# Adafruit_HMC5883L_Compas.net
KiCad netlist of a schematic drawn in EAGLE
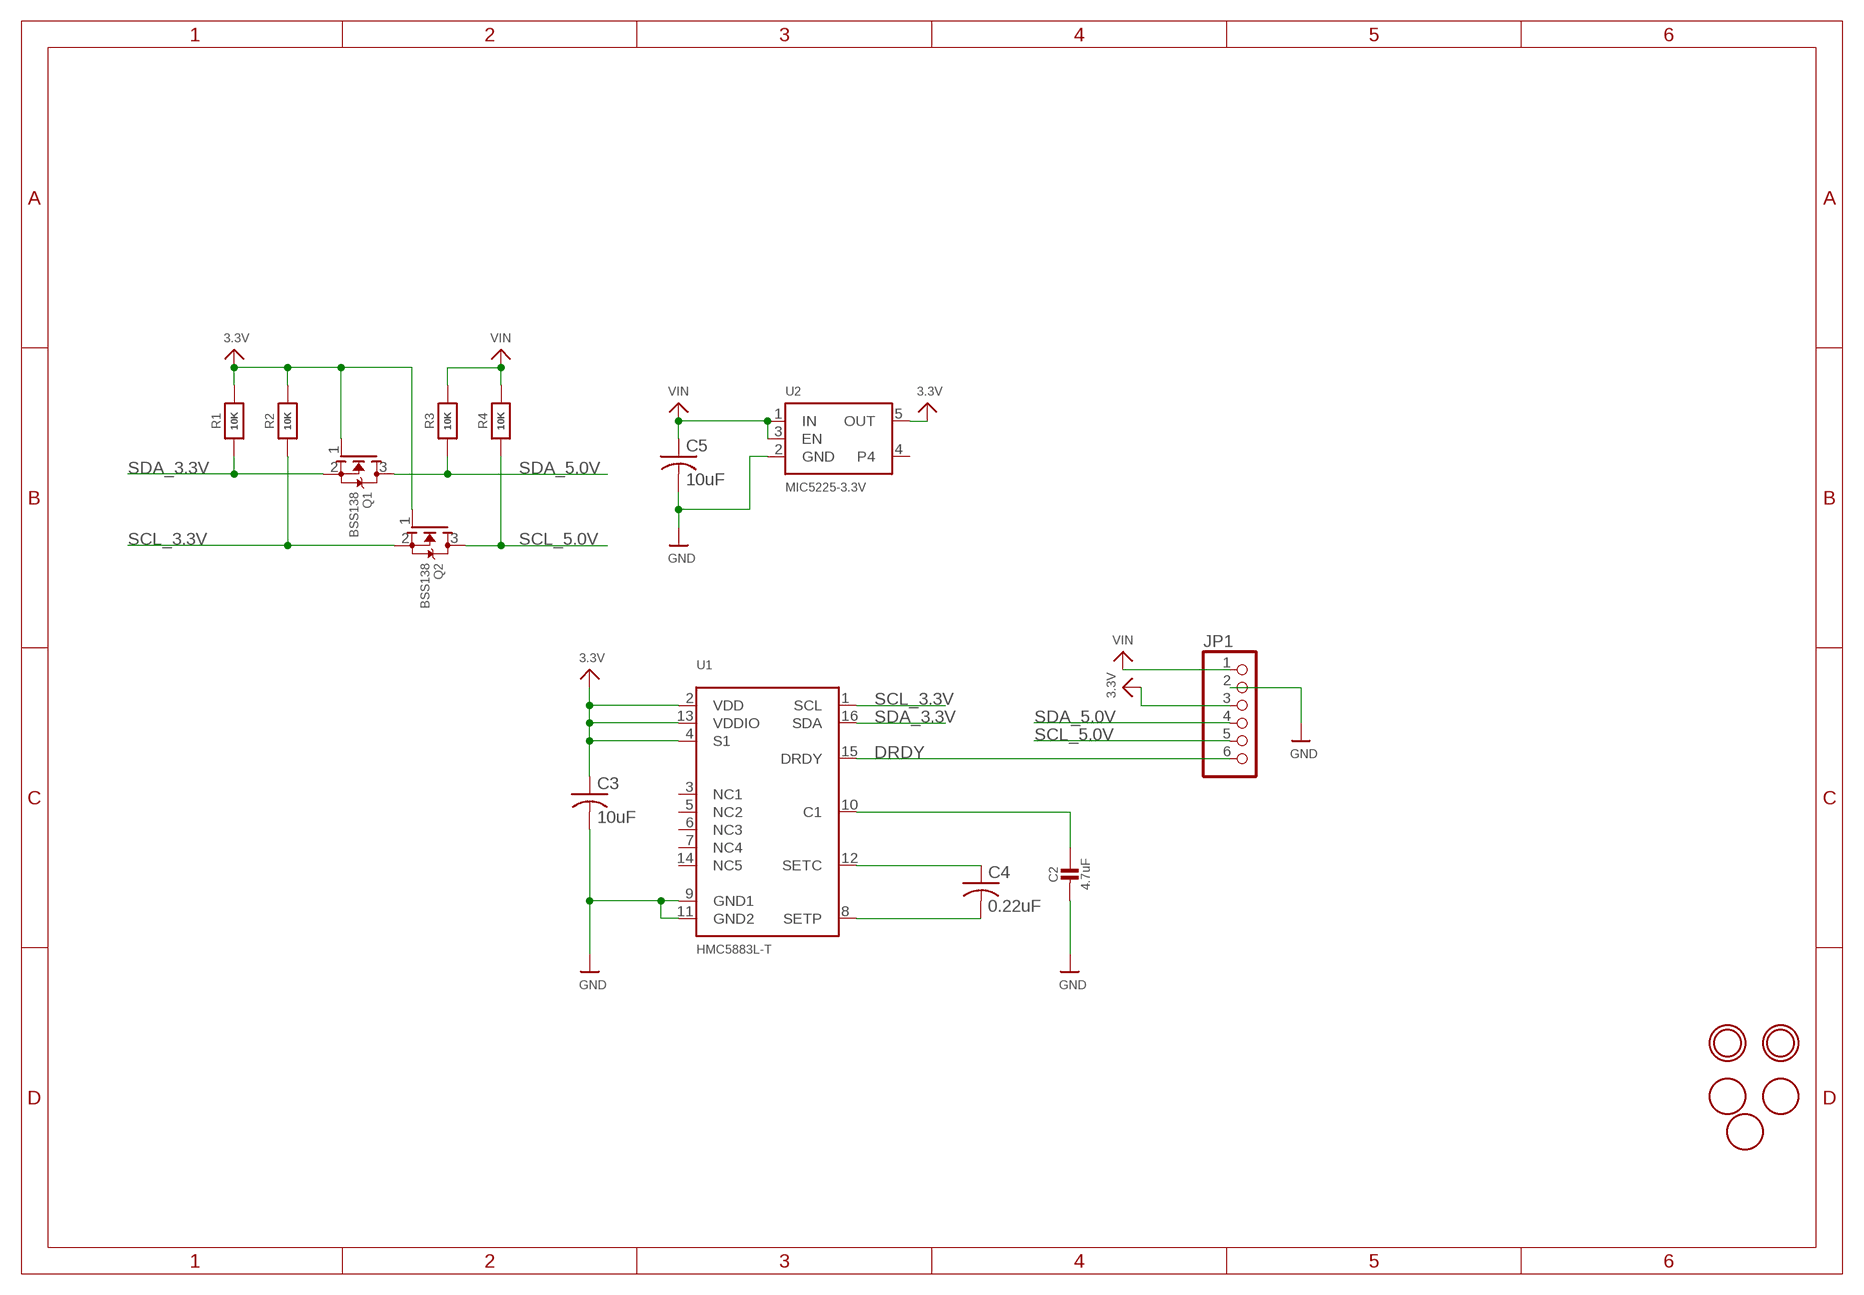
[diagram p0: schematic, sheet 1]

(export (version "E")
  (design (tool "Eeschema 10.0.6"))
  (components
    (comp (ref "C2")
      (value "4.7uF")
      (footprint "eagle-import:0805_10MGAP")
      (libsource (lib "eagle-import") (part "CAP_CERAMIC0805_10MGAP"))
    )
    (comp (ref "C3")
      (value "10uF")
      (footprint "eagle-import:C0805")
      (libsource (lib "eagle-import") (part "C-USC0805"))
    )
    (comp (ref "C4")
      (value "0.22uF")
      (footprint "eagle-import:C0805")
      (libsource (lib "eagle-import") (part "C-USC0805"))
    )
    (comp (ref "C5")
      (value "10uF")
      (footprint "eagle-import:C0805")
      (libsource (lib "eagle-import") (part "C-USC0805"))
    )
    (comp (ref "JP1")
      (value "HEADER-1X676MIL")
      (footprint "eagle-import:1X06_ROUND_76")
      (libsource (lib "eagle-import") (part "HEADER-1X676MIL"))
    )
    (comp (ref "Q1")
      (value "BSS138")
      (footprint "eagle-import:SOT23-WIDE")
      (libsource (lib "eagle-import") (part "MOSFET-NWIDE"))
    )
    (comp (ref "Q2")
      (value "BSS138")
      (footprint "eagle-import:SOT23-WIDE")
      (libsource (lib "eagle-import") (part "MOSFET-NWIDE"))
    )
    (comp (ref "R1")
      (value "10K")
      (footprint "eagle-import:_0805MP")
      (libsource (lib "eagle-import") (part "RESISTOR_0805MP"))
    )
    (comp (ref "R2")
      (value "10K")
      (footprint "eagle-import:_0805MP")
      (libsource (lib "eagle-import") (part "RESISTOR_0805MP"))
    )
    (comp (ref "R3")
      (value "10K")
      (footprint "eagle-import:0805-NO")
      (libsource (lib "eagle-import") (part "RESISTOR0805_NOOUTLINE"))
    )
    (comp (ref "R4")
      (value "10K")
      (footprint "eagle-import:0805-NO")
      (libsource (lib "eagle-import") (part "RESISTOR0805_NOOUTLINE"))
    )
    (comp (ref "U$8")
      (value "MOUNTINGHOLE2.5")
      (footprint "eagle-import:MOUNTINGHOLE_2.5_PLATED")
      (libsource (lib "eagle-import") (part "MOUNTINGHOLE2.5"))
    )
    (comp (ref "U$9")
      (value "MOUNTINGHOLE2.5")
      (footprint "eagle-import:MOUNTINGHOLE_2.5_PLATED")
      (libsource (lib "eagle-import") (part "MOUNTINGHOLE2.5"))
    )
    (comp (ref "U$10")
      (value "FIDUCIAL")
      (footprint "eagle-import:FIDUCIAL_1MM")
      (libsource (lib "eagle-import") (part "FIDUCIAL"))
    )
    (comp (ref "U$11")
      (value "FIDUCIAL")
      (footprint "eagle-import:FIDUCIAL_1MM")
      (libsource (lib "eagle-import") (part "FIDUCIAL"))
    )
    (comp (ref "U$12")
      (value "FIDUCIAL")
      (footprint "eagle-import:FIDUCIAL_1MM")
      (libsource (lib "eagle-import") (part "FIDUCIAL"))
    )
    (comp (ref "U1")
      (value "HMC5883L-T")
      (footprint "eagle-import:HMC5883L")
      (libsource (lib "eagle-import") (part "HMC5883L"))
    )
    (comp (ref "U2")
      (value "MIC5225-3.3V")
      (footprint "eagle-import:SOT23-5")
      (libsource (lib "eagle-import") (part "VREG_SOT23-5"))
    )
  )
  (nets
    (net (code "1") (name "/DRDY") (class "Default")
      (node (ref "JP1") (pin "6") (pinfunction "6_6") (pintype "passive"))
      (node (ref "U1") (pin "15") (pinfunction "DRDY_15") (pintype "bidirectional"))
    )
    (net (code "2") (name "/SCL_3.3V") (class "Default")
      (node (ref "Q2") (pin "2") (pinfunction "S_2") (pintype "bidirectional"))
      (node (ref "R2") (pin "1") (pinfunction "1_1") (pintype "passive"))
      (node (ref "U1") (pin "1") (pinfunction "SCL_1") (pintype "bidirectional"))
    )
    (net (code "3") (name "/SCL_5.0V") (class "Default")
      (node (ref "JP1") (pin "5") (pinfunction "5_5") (pintype "passive"))
      (node (ref "Q2") (pin "3") (pinfunction "D_3") (pintype "bidirectional"))
      (node (ref "R4") (pin "1") (pinfunction "1_1") (pintype "passive"))
    )
    (net (code "4") (name "/SDA_3.3V") (class "Default")
      (node (ref "Q1") (pin "2") (pinfunction "S_2") (pintype "bidirectional"))
      (node (ref "R1") (pin "1") (pinfunction "1_1") (pintype "passive"))
      (node (ref "U1") (pin "16") (pinfunction "SDA_16") (pintype "bidirectional"))
    )
    (net (code "5") (name "/SDA_5.0V") (class "Default")
      (node (ref "JP1") (pin "4") (pinfunction "4_4") (pintype "passive"))
      (node (ref "Q1") (pin "3") (pinfunction "D_3") (pintype "bidirectional"))
      (node (ref "R3") (pin "1") (pinfunction "1_1") (pintype "passive"))
    )
    (net (code "6") (name "3.3V") (class "Default")
      (node (ref "C3") (pin "1") (pinfunction "1_1") (pintype "passive"))
      (node (ref "JP1") (pin "3") (pinfunction "3_3") (pintype "passive"))
      (node (ref "Q1") (pin "1") (pinfunction "G_1") (pintype "bidirectional"))
      (node (ref "Q2") (pin "1") (pinfunction "G_1") (pintype "bidirectional"))
      (node (ref "R1") (pin "2") (pinfunction "2_2") (pintype "passive"))
      (node (ref "R2") (pin "2") (pinfunction "2_2") (pintype "passive"))
      (node (ref "U1") (pin "13") (pinfunction "VDDIO_13") (pintype "bidirectional"))
      (node (ref "U1") (pin "2") (pinfunction "VDD_2") (pintype "bidirectional"))
      (node (ref "U1") (pin "4") (pinfunction "S1_4") (pintype "bidirectional"))
      (node (ref "U2") (pin "5") (pinfunction "OUT_5") (pintype "power_in"))
    )
    (net (code "7") (name "GND") (class "Default")
      (node (ref "C2") (pin "2") (pinfunction "2_2") (pintype "passive"))
      (node (ref "C3") (pin "2") (pinfunction "2_2") (pintype "passive"))
      (node (ref "C5") (pin "2") (pinfunction "2_2") (pintype "passive"))
      (node (ref "JP1") (pin "2") (pinfunction "2_2") (pintype "passive"))
      (node (ref "U1") (pin "11") (pinfunction "GND2_11") (pintype "bidirectional"))
      (node (ref "U1") (pin "9") (pinfunction "GND1_9") (pintype "bidirectional"))
      (node (ref "U2") (pin "2") (pinfunction "GND_2") (pintype "power_in"))
    )
    (net (code "8") (name "Net-(U1-C1)") (class "Default")
      (node (ref "C2") (pin "1") (pinfunction "1_1") (pintype "passive"))
      (node (ref "U1") (pin "10") (pinfunction "C1_10") (pintype "bidirectional"))
    )
    (net (code "9") (name "Net-(U1-SETC)") (class "Default")
      (node (ref "C4") (pin "1") (pinfunction "1_1") (pintype "passive"))
      (node (ref "U1") (pin "12") (pinfunction "SETC_12") (pintype "bidirectional"))
    )
    (net (code "10") (name "Net-(U1-SETP)") (class "Default")
      (node (ref "C4") (pin "2") (pinfunction "2_2") (pintype "passive"))
      (node (ref "U1") (pin "8") (pinfunction "SETP_8") (pintype "bidirectional"))
    )
    (net (code "11") (name "VIN") (class "Default")
      (node (ref "C5") (pin "1") (pinfunction "1_1") (pintype "passive"))
      (node (ref "JP1") (pin "1") (pinfunction "1_1") (pintype "passive"))
      (node (ref "R3") (pin "2") (pinfunction "2_2") (pintype "passive"))
      (node (ref "R4") (pin "2") (pinfunction "2_2") (pintype "passive"))
      (node (ref "U2") (pin "1") (pinfunction "IN_1") (pintype "power_in"))
      (node (ref "U2") (pin "3") (pinfunction "EN_3") (pintype "input"))
    )
    (net (code "12") (name "unconnected-(U1-NC1-Pad3)") (class "Default")
      (node (ref "U1") (pin "3") (pinfunction "NC1_3") (pintype "bidirectional"))
    )
    (net (code "13") (name "unconnected-(U1-NC2-Pad5)") (class "Default")
      (node (ref "U1") (pin "5") (pinfunction "NC2_5") (pintype "bidirectional"))
    )
    (net (code "14") (name "unconnected-(U1-NC3-Pad6)") (class "Default")
      (node (ref "U1") (pin "6") (pinfunction "NC3_6") (pintype "bidirectional"))
    )
    (net (code "15") (name "unconnected-(U1-NC4-Pad7)") (class "Default")
      (node (ref "U1") (pin "7") (pinfunction "NC4_7") (pintype "bidirectional"))
    )
    (net (code "16") (name "unconnected-(U1-NC5-Pad14)") (class "Default")
      (node (ref "U1") (pin "14") (pinfunction "NC5_14") (pintype "bidirectional"))
    )
    (net (code "17") (name "unconnected-(U2-P4-Pad4)") (class "Default")
      (node (ref "U2") (pin "4") (pinfunction "P4_4") (pintype "bidirectional"))
    )
  )
)
